# smallDevV2.net
KiCad netlist of a schematic drawn in EAGLE
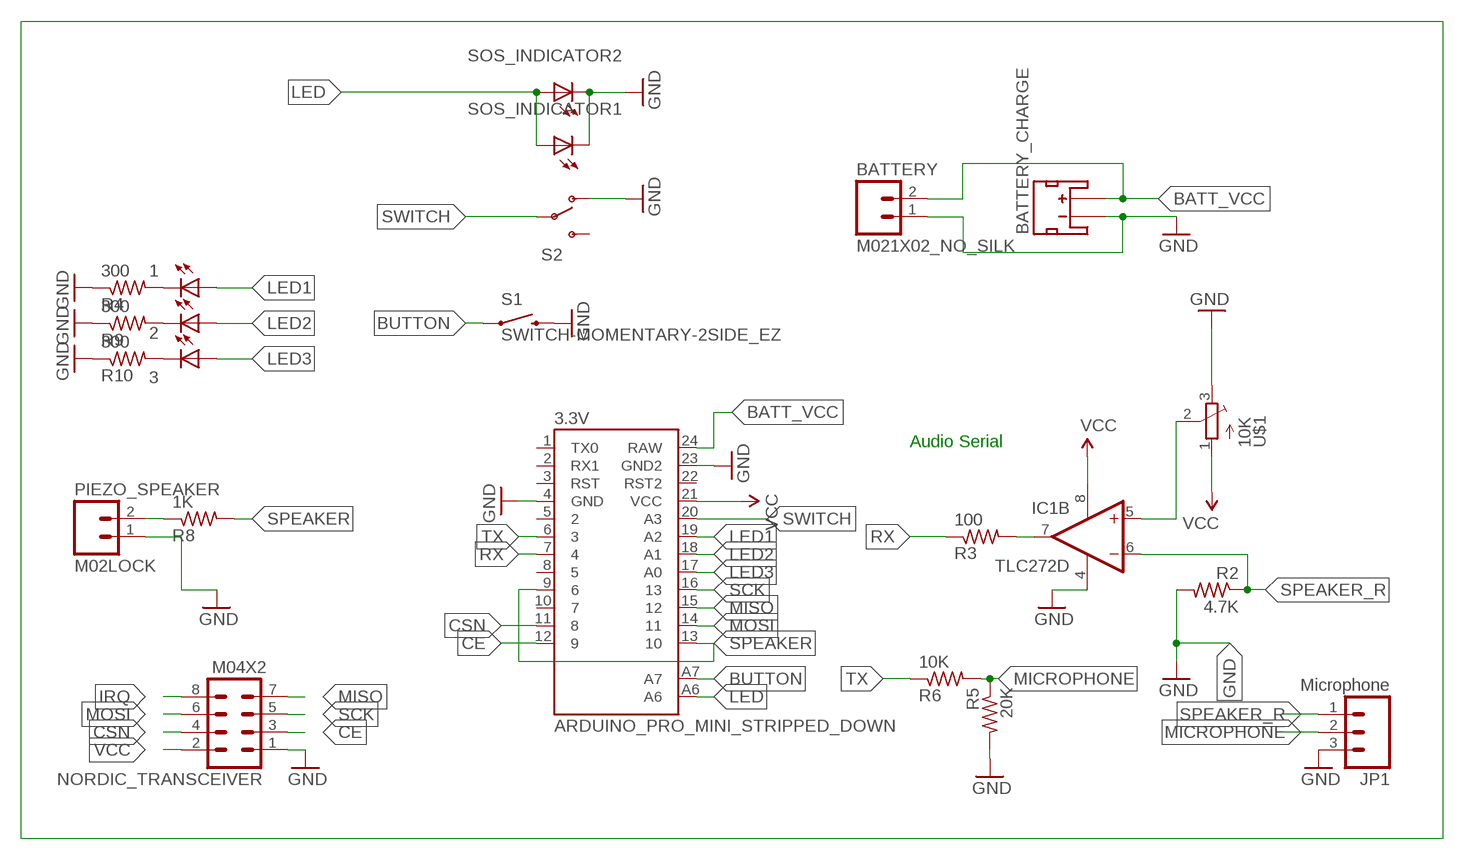
[diagram p0: schematic, sheet 1]

(export (version "E")
  (design (tool "Eeschema 10.0.6"))
  (components
    (comp (ref "1")
      (value "LEDCHIP-LED0805")
      (footprint "eagle-import:CHIP-LED0805")
      (libsource (lib "eagle-import") (part "LEDCHIP-LED0805"))
    )
    (comp (ref "2")
      (value "LEDCHIP-LED0805")
      (footprint "eagle-import:CHIP-LED0805")
      (libsource (lib "eagle-import") (part "LEDCHIP-LED0805"))
    )
    (comp (ref "3")
      (value "LEDCHIP-LED0805")
      (footprint "eagle-import:CHIP-LED0805")
      (libsource (lib "eagle-import") (part "LEDCHIP-LED0805"))
    )
    (comp (ref "3.3V")
      (value "ARDUINO_PRO_MINI_STRIPPED_DOWN")
      (footprint "eagle-import:ARDUINO_PRO_MINI_STRIPPED_DOWN")
      (libsource (lib "eagle-import") (part "ARDUINO_PRO_MINI_STRIPPED_DOWN"))
    )
    (comp (ref "BATTERY")
      (value "M021X02_NO_SILK")
      (footprint "eagle-import:1X02_NO_SILK")
      (libsource (lib "eagle-import") (part "M021X02_NO_SILK"))
    )
    (comp (ref "BATTERY_CHARGE")
      (value "JST_2MM_MALE")
      (footprint "eagle-import:JST-2-SMD")
      (libsource (lib "eagle-import") (part "JST_2MM_MALE"))
    )
    (comp (ref "IC1")
      (value "TLC272D")
      (footprint "eagle-import:SO08")
      (libsource (lib "eagle-import") (part "TLC272D"))
    )
    (comp (ref "JP1")
      (value "Microphone")
      (footprint "eagle-import:1X03_LOCK")
      (libsource (lib "eagle-import") (part "M03LOCK"))
    )
    (comp (ref "NORDIC_TRANSCEIVER")
      (value "M04X2")
      (footprint "eagle-import:2X4")
      (libsource (lib "eagle-import") (part "M04X2"))
    )
    (comp (ref "PIEZO_SPEAKER")
      (value "M02LOCK")
      (footprint "eagle-import:1X02_LOCK")
      (libsource (lib "eagle-import") (part "M02LOCK"))
    )
    (comp (ref "R2")
      (value "4.7K")
      (footprint "eagle-import:M0805")
      (libsource (lib "eagle-import") (part "R-US_M0805"))
    )
    (comp (ref "R3")
      (value "100")
      (footprint "eagle-import:M0805")
      (libsource (lib "eagle-import") (part "R-US_M0805"))
    )
    (comp (ref "R4")
      (value "300")
      (footprint "eagle-import:M0805")
      (libsource (lib "eagle-import") (part "R-US_M0805"))
    )
    (comp (ref "R5")
      (value "20K")
      (footprint "eagle-import:M0805")
      (libsource (lib "eagle-import") (part "R-US_M0805"))
    )
    (comp (ref "R6")
      (value "10K")
      (footprint "eagle-import:M0805")
      (libsource (lib "eagle-import") (part "R-US_M0805"))
    )
    (comp (ref "R8")
      (value "1K")
      (footprint "eagle-import:M0805")
      (libsource (lib "eagle-import") (part "R-US_M0805"))
    )
    (comp (ref "R9")
      (value "300")
      (footprint "eagle-import:M0805")
      (libsource (lib "eagle-import") (part "R-US_M0805"))
    )
    (comp (ref "R10")
      (value "300")
      (footprint "eagle-import:M0805")
      (libsource (lib "eagle-import") (part "R-US_M0805"))
    )
    (comp (ref "S1")
      (value "SWITCH-MOMENTARY-2SIDE_EZ")
      (footprint "eagle-import:TACTILE-PTH-SIDEEZ")
      (libsource (lib "eagle-import") (part "SWITCH-MOMENTARY-2SIDE_EZ"))
    )
    (comp (ref "S2")
      (value "SWITCH-SPDT-SMD-A")
      (footprint "eagle-import:SWITCH-SPST-SMD-A")
      (libsource (lib "eagle-import") (part "SWITCH-SPDT-SMD-A"))
    )
    (comp (ref "SOS_INDICATOR1")
      (value "LEDCHIP-LED0805")
      (footprint "eagle-import:CHIP-LED0805")
      (libsource (lib "eagle-import") (part "LEDCHIP-LED0805"))
    )
    (comp (ref "SOS_INDICATOR2")
      (value "LEDCHIP-LED0805")
      (footprint "eagle-import:CHIP-LED0805")
      (libsource (lib "eagle-import") (part "LEDCHIP-LED0805"))
    )
    (comp (ref "U$1")
      (value "10K")
      (footprint "eagle-import:TC33X")
      (libsource (lib "eagle-import") (part "TRIMPOTTC33X"))
    )
  )
  (nets
    (net (code "1") (name "BATT_VCC") (class "Default")
      (node (ref "3.3V") (pin "24") (pinfunction "RAW_24") (pintype "bidirectional"))
      (node (ref "BATTERY") (pin "2") (pinfunction "2_2") (pintype "passive"))
      (node (ref "BATTERY_CHARGE") (pin "2") (pinfunction "+_2") (pintype "bidirectional"))
    )
    (net (code "2") (name "BUTTON") (class "Default")
      (node (ref "3.3V") (pin "A7") (pinfunction "A7_A7") (pintype "bidirectional"))
      (node (ref "S1") (pin "1") (pinfunction "1_1") (pintype "passive"))
    )
    (net (code "3") (name "CE") (class "Default")
      (node (ref "3.3V") (pin "12") (pinfunction "9_12") (pintype "bidirectional"))
      (node (ref "NORDIC_TRANSCEIVER") (pin "3") (pinfunction "3_3") (pintype "passive"))
    )
    (net (code "4") (name "CSN") (class "Default")
      (node (ref "3.3V") (pin "11") (pinfunction "8_11") (pintype "bidirectional"))
      (node (ref "NORDIC_TRANSCEIVER") (pin "4") (pinfunction "4_4") (pintype "passive"))
    )
    (net (code "5") (name "GND") (class "Default")
      (node (ref "3.3V") (pin "23") (pinfunction "GND2_23") (pintype "bidirectional"))
      (node (ref "3.3V") (pin "4") (pinfunction "GND_4") (pintype "bidirectional"))
      (node (ref "BATTERY") (pin "1") (pinfunction "1_1") (pintype "passive"))
      (node (ref "BATTERY_CHARGE") (pin "1") (pinfunction "-_1") (pintype "bidirectional"))
      (node (ref "IC1") (pin "4") (pinfunction "V-_4") (pintype "power_in"))
      (node (ref "JP1") (pin "3") (pinfunction "3_3") (pintype "passive"))
      (node (ref "NORDIC_TRANSCEIVER") (pin "1") (pinfunction "1_1") (pintype "passive"))
      (node (ref "PIEZO_SPEAKER") (pin "1") (pinfunction "1_1") (pintype "passive"))
      (node (ref "R10") (pin "1") (pinfunction "1_1") (pintype "passive"))
      (node (ref "R2") (pin "2") (pinfunction "2_2") (pintype "passive"))
      (node (ref "R4") (pin "1") (pinfunction "1_1") (pintype "passive"))
      (node (ref "R5") (pin "2") (pinfunction "2_2") (pintype "passive"))
      (node (ref "R9") (pin "1") (pinfunction "1_1") (pintype "passive"))
      (node (ref "S1") (pin "2") (pinfunction "2_2") (pintype "passive"))
      (node (ref "S2") (pin "1") (pinfunction "O_1") (pintype "passive"))
      (node (ref "SOS_INDICATOR1") (pin "C") (pinfunction "C_C") (pintype "passive"))
      (node (ref "SOS_INDICATOR2") (pin "C") (pinfunction "C_C") (pintype "passive"))
      (node (ref "U$1") (pin "3") (pinfunction "E_3") (pintype "passive"))
    )
    (net (code "6") (name "IRQ") (class "Default")
      (node (ref "NORDIC_TRANSCEIVER") (pin "8") (pinfunction "8_8") (pintype "passive"))
    )
    (net (code "7") (name "LED") (class "Default")
      (node (ref "3.3V") (pin "A6") (pinfunction "A6_A6") (pintype "bidirectional"))
      (node (ref "SOS_INDICATOR1") (pin "A") (pinfunction "A_A") (pintype "passive"))
      (node (ref "SOS_INDICATOR2") (pin "A") (pinfunction "A_A") (pintype "passive"))
    )
    (net (code "8") (name "LED1") (class "Default")
      (node (ref "1") (pin "A") (pinfunction "A_A") (pintype "passive"))
      (node (ref "3.3V") (pin "19") (pinfunction "A2_19") (pintype "bidirectional"))
    )
    (net (code "9") (name "LED2") (class "Default")
      (node (ref "2") (pin "A") (pinfunction "A_A") (pintype "passive"))
      (node (ref "3.3V") (pin "18") (pinfunction "A1_18") (pintype "bidirectional"))
    )
    (net (code "10") (name "LED3") (class "Default")
      (node (ref "3") (pin "A") (pinfunction "A_A") (pintype "passive"))
      (node (ref "3.3V") (pin "17") (pinfunction "A0_17") (pintype "bidirectional"))
    )
    (net (code "11") (name "MICROPHONE") (class "Default")
      (node (ref "JP1") (pin "2") (pinfunction "2_2") (pintype "passive"))
      (node (ref "R5") (pin "1") (pinfunction "1_1") (pintype "passive"))
      (node (ref "R6") (pin "2") (pinfunction "2_2") (pintype "passive"))
    )
    (net (code "12") (name "MISO") (class "Default")
      (node (ref "3.3V") (pin "15") (pinfunction "12_15") (pintype "bidirectional"))
      (node (ref "NORDIC_TRANSCEIVER") (pin "7") (pinfunction "7_7") (pintype "passive"))
    )
    (net (code "13") (name "MOSI") (class "Default")
      (node (ref "3.3V") (pin "14") (pinfunction "11_14") (pintype "bidirectional"))
      (node (ref "NORDIC_TRANSCEIVER") (pin "6") (pinfunction "6_6") (pintype "passive"))
    )
    (net (code "14") (name "Net-(1-PadC)") (class "Default")
      (node (ref "1") (pin "C") (pinfunction "C_C") (pintype "passive"))
      (node (ref "R4") (pin "2") (pinfunction "2_2") (pintype "passive"))
    )
    (net (code "15") (name "Net-(2-PadC)") (class "Default")
      (node (ref "2") (pin "C") (pinfunction "C_C") (pintype "passive"))
      (node (ref "R9") (pin "2") (pinfunction "2_2") (pintype "passive"))
    )
    (net (code "16") (name "Net-(3-PadC)") (class "Default")
      (node (ref "3") (pin "C") (pinfunction "C_C") (pintype "passive"))
      (node (ref "R10") (pin "2") (pinfunction "2_2") (pintype "passive"))
    )
    (net (code "17") (name "Net-(IC1B-+IN)") (class "Default")
      (node (ref "IC1") (pin "5") (pinfunction "+IN_5") (pintype "input"))
      (node (ref "U$1") (pin "2") (pinfunction "S_2") (pintype "passive"))
    )
    (net (code "18") (name "Net-(IC1B-OUT)") (class "Default")
      (node (ref "IC1") (pin "7") (pinfunction "OUT_7") (pintype "output"))
      (node (ref "R3") (pin "2") (pinfunction "2_2") (pintype "passive"))
    )
    (net (code "19") (name "Net-(PIEZO_SPEAKER-Pad2)") (class "Default")
      (node (ref "PIEZO_SPEAKER") (pin "2") (pinfunction "2_2") (pintype "passive"))
      (node (ref "R8") (pin "1") (pinfunction "1_1") (pintype "passive"))
    )
    (net (code "20") (name "RX") (class "Default")
      (node (ref "3.3V") (pin "7") (pinfunction "4_7") (pintype "bidirectional"))
      (node (ref "R3") (pin "1") (pinfunction "1_1") (pintype "passive"))
    )
    (net (code "21") (name "SCK") (class "Default")
      (node (ref "3.3V") (pin "16") (pinfunction "13_16") (pintype "bidirectional"))
      (node (ref "NORDIC_TRANSCEIVER") (pin "5") (pinfunction "5_5") (pintype "passive"))
    )
    (net (code "22") (name "SPEAKER") (class "Default")
      (node (ref "3.3V") (pin "13") (pinfunction "10_13") (pintype "bidirectional"))
      (node (ref "3.3V") (pin "9") (pinfunction "6_9") (pintype "bidirectional"))
      (node (ref "R8") (pin "2") (pinfunction "2_2") (pintype "passive"))
    )
    (net (code "23") (name "SPEAKER_R") (class "Default")
      (node (ref "IC1") (pin "6") (pinfunction "-IN_6") (pintype "input"))
      (node (ref "JP1") (pin "1") (pinfunction "1_1") (pintype "passive"))
      (node (ref "R2") (pin "1") (pinfunction "1_1") (pintype "passive"))
    )
    (net (code "24") (name "SWITCH") (class "Default")
      (node (ref "3.3V") (pin "20") (pinfunction "A3_20") (pintype "bidirectional"))
      (node (ref "S2") (pin "2") (pinfunction "P_2") (pintype "passive"))
    )
    (net (code "25") (name "TX") (class "Default")
      (node (ref "3.3V") (pin "6") (pinfunction "3_6") (pintype "bidirectional"))
      (node (ref "R6") (pin "1") (pinfunction "1_1") (pintype "passive"))
    )
    (net (code "26") (name "VCC") (class "Default")
      (node (ref "3.3V") (pin "21") (pinfunction "VCC_21") (pintype "bidirectional"))
      (node (ref "IC1") (pin "8") (pinfunction "V+_8") (pintype "power_in"))
      (node (ref "NORDIC_TRANSCEIVER") (pin "2") (pinfunction "2_2") (pintype "passive"))
      (node (ref "U$1") (pin "1") (pinfunction "A_1") (pintype "passive"))
    )
    (net (code "27") (name "unconnected-(3.3V-2-Pad5)") (class "Default")
      (node (ref "3.3V") (pin "5") (pinfunction "2_5") (pintype "bidirectional"))
    )
    (net (code "28") (name "unconnected-(3.3V-5-Pad8)") (class "Default")
      (node (ref "3.3V") (pin "8") (pinfunction "5_8") (pintype "bidirectional"))
    )
    (net (code "29") (name "unconnected-(3.3V-7-Pad10)") (class "Default")
      (node (ref "3.3V") (pin "10") (pinfunction "7_10") (pintype "bidirectional"))
    )
    (net (code "30") (name "unconnected-(3.3V-RST-Pad3)") (class "Default")
      (node (ref "3.3V") (pin "3") (pinfunction "RST_3") (pintype "bidirectional"))
    )
    (net (code "31") (name "unconnected-(3.3V-RST2-Pad22)") (class "Default")
      (node (ref "3.3V") (pin "22") (pinfunction "RST2_22") (pintype "bidirectional"))
    )
    (net (code "32") (name "unconnected-(3.3V-RX1-Pad2)") (class "Default")
      (node (ref "3.3V") (pin "2") (pinfunction "RX1_2") (pintype "bidirectional"))
    )
    (net (code "33") (name "unconnected-(3.3V-TX0-Pad1)") (class "Default")
      (node (ref "3.3V") (pin "1") (pinfunction "TX0_1") (pintype "bidirectional"))
    )
    (net (code "34") (name "unconnected-(BATTERY_CHARGE-PAD1-PadNC1)") (class "Default")
      (node (ref "BATTERY_CHARGE") (pin "NC1") (pinfunction "PAD1_NC1") (pintype "bidirectional"))
    )
    (net (code "35") (name "unconnected-(BATTERY_CHARGE-PAD2-PadNC2)") (class "Default")
      (node (ref "BATTERY_CHARGE") (pin "NC2") (pinfunction "PAD2_NC2") (pintype "bidirectional"))
    )
    (net (code "36") (name "unconnected-(S2-S-Pad3)") (class "Default")
      (node (ref "S2") (pin "3") (pinfunction "S_3") (pintype "passive"))
    )
  )
)
